# firing-motor.net
KiCad netlist of a schematic drawn in EAGLE
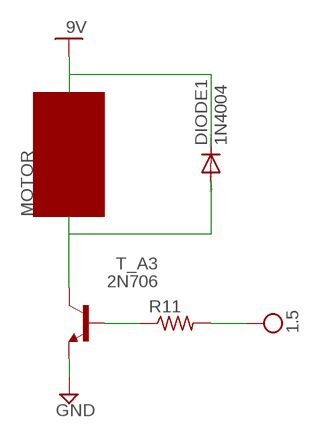
[diagram p0: schematic, sheet 1]

(export (version "E")
  (design (tool "Eeschema 10.0.6"))
  (components
    (comp (ref "DIODE1")
      (value "1N4004")
      (footprint "eagle-import:DO41-10")
      (libsource (lib "eagle-import") (part "1N4004"))
    )
    (comp (ref "R11")
      (value "R-US_0204/2V")
      (footprint "eagle-import:0204V")
      (libsource (lib "eagle-import") (part "R-US_0204/2V"))
    )
    (comp (ref "T_A3")
      (value "2N706")
      (footprint "eagle-import:TO18")
      (libsource (lib "eagle-import") (part "2N706"))
    )
  )
  (nets
    (net (code "1") (name "1.5") (class "Default")
      (node (ref "R11") (pin "2") (pinfunction "2_2") (pintype "passive"))
    )
    (net (code "2") (name "9V") (class "Default")
      (node (ref "DIODE1") (pin "C") (pinfunction "C_C") (pintype "passive"))
      (node (ref "T_A3") (pin "1") (pinfunction "E_1") (pintype "passive"))
    )
    (net (code "3") (name "Net-(T_A3-B)") (class "Default")
      (node (ref "R11") (pin "1") (pinfunction "1_1") (pintype "passive"))
      (node (ref "T_A3") (pin "2") (pinfunction "B_2") (pintype "passive"))
    )
    (net (code "4") (name "Net-(T_A3-C)") (class "Default")
      (node (ref "DIODE1") (pin "A") (pinfunction "A_A") (pintype "passive"))
      (node (ref "T_A3") (pin "3") (pinfunction "C_3") (pintype "passive"))
    )
  )
)
